# G8CntlA_109_5x19.net
KiCad netlist of a schematic drawn in EAGLE
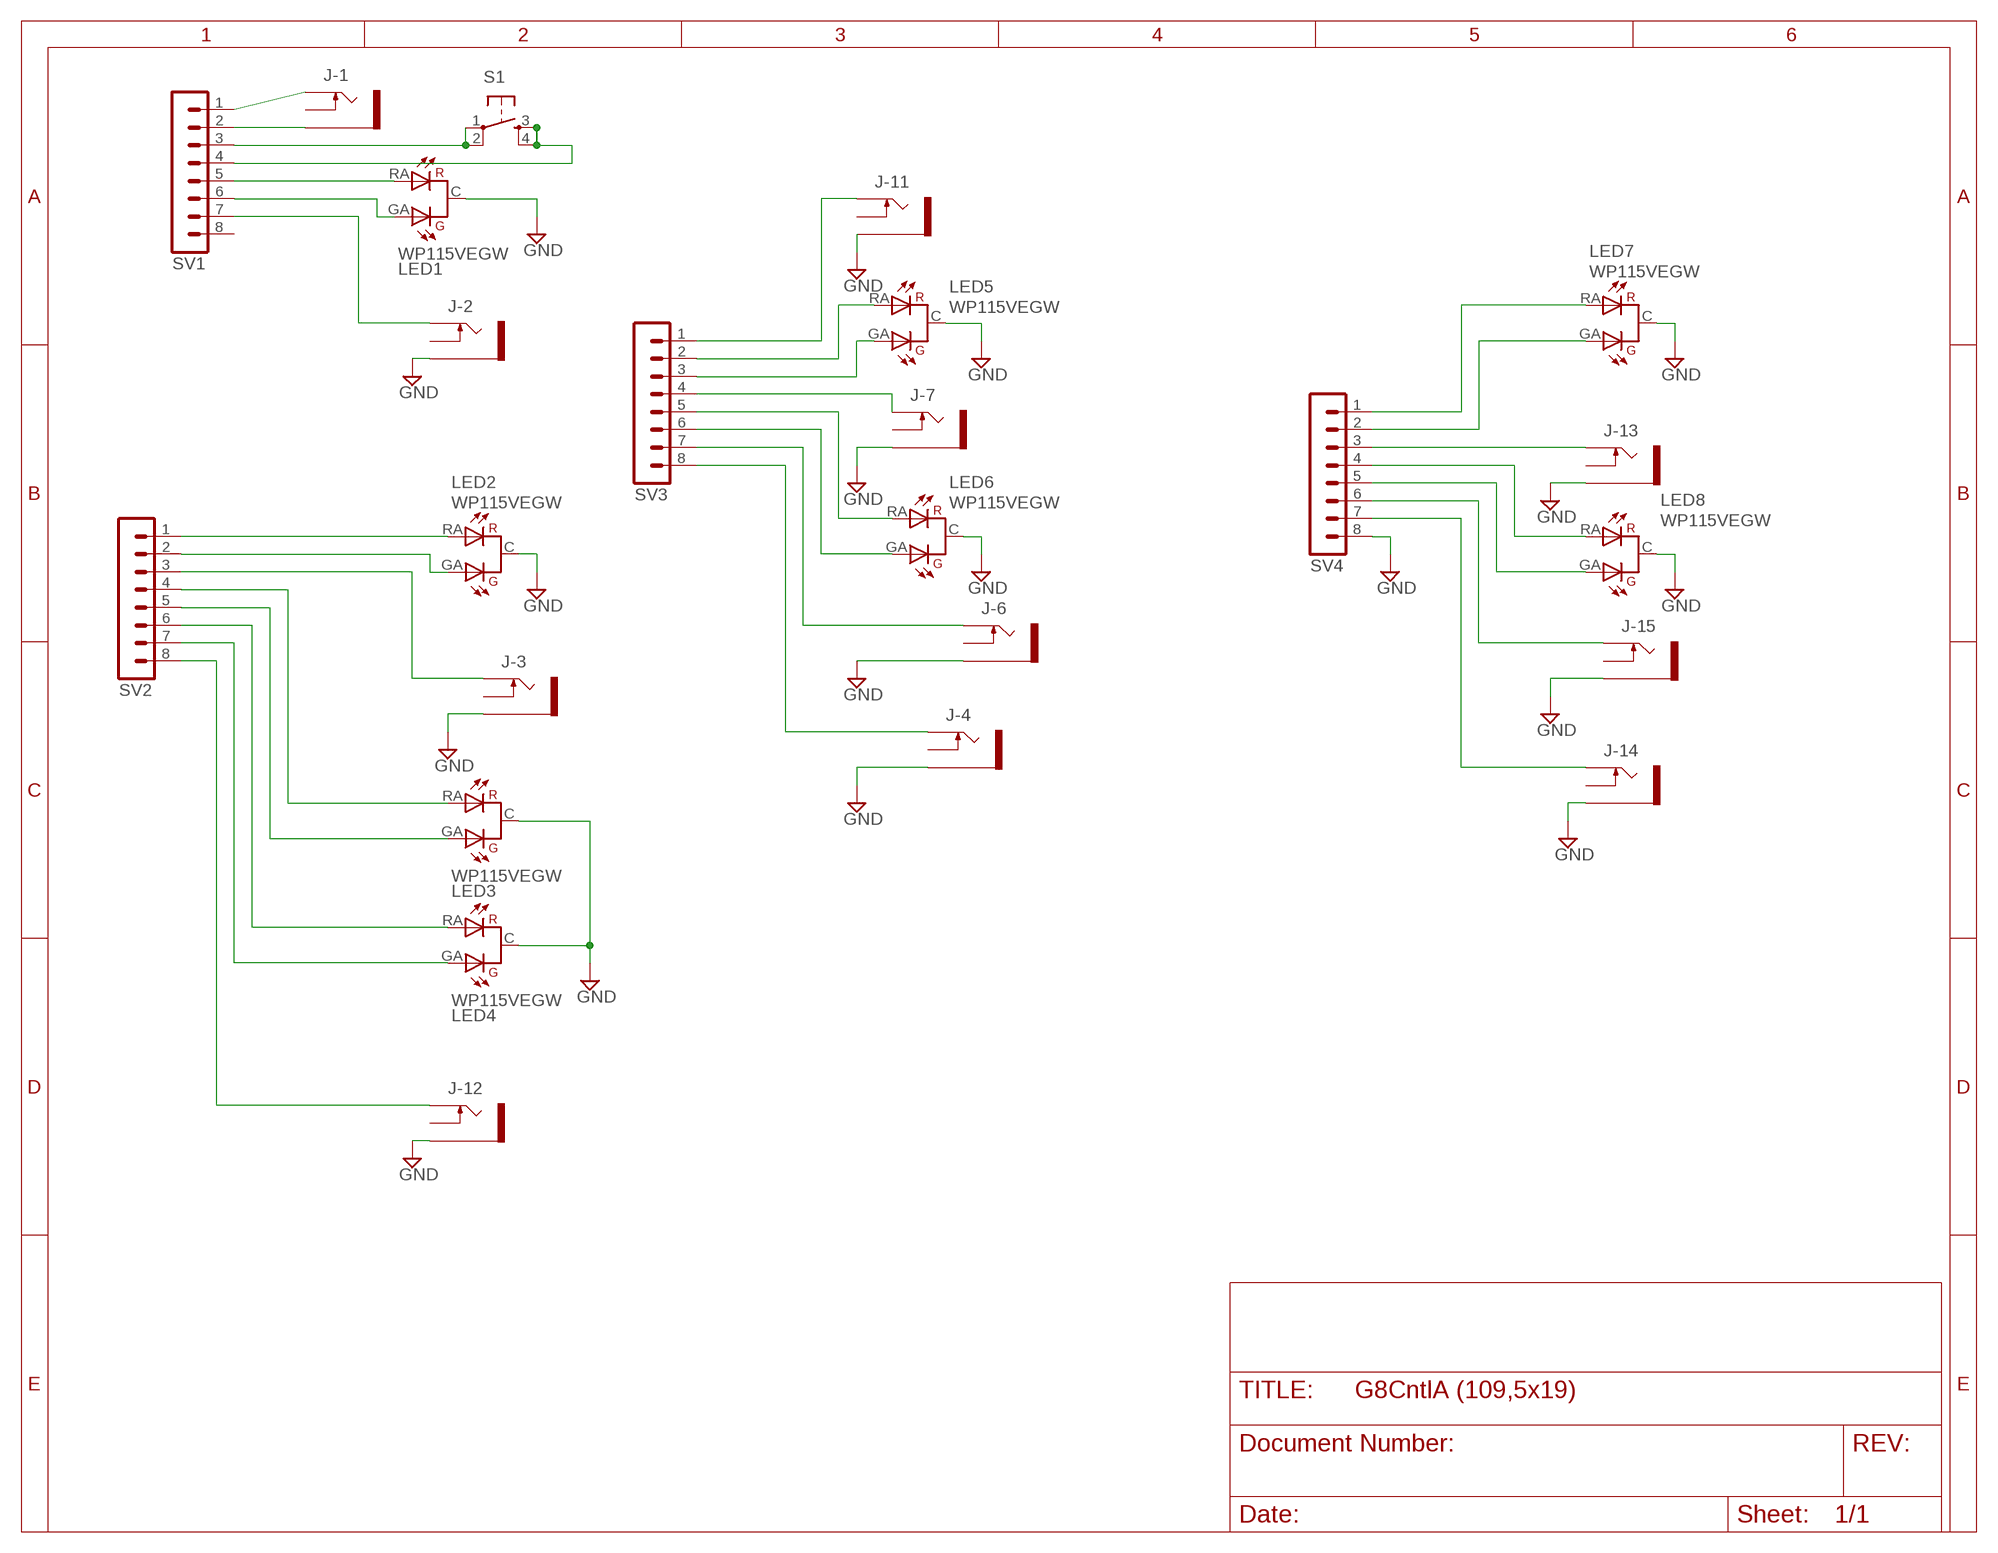
[diagram p0: schematic, sheet 1]

(export (version "E")
  (design (tool "Eeschema 10.0.6"))
  (components
    (comp (ref "J-1")
      (value "THONKICONNNEW")
      (footprint "eagle-import:WQP-PJ301M-12_JACK")
      (libsource (lib "eagle-import") (part "THONKICONNNEW"))
    )
    (comp (ref "J-2")
      (value "THONKICONNNEW")
      (footprint "eagle-import:WQP-PJ301M-12_JACK")
      (libsource (lib "eagle-import") (part "THONKICONNNEW"))
    )
    (comp (ref "J-3")
      (value "THONKICONNNEW")
      (footprint "eagle-import:WQP-PJ301M-12_JACK")
      (libsource (lib "eagle-import") (part "THONKICONNNEW"))
    )
    (comp (ref "J-4")
      (value "THONKICONNNEW")
      (footprint "eagle-import:WQP-PJ301M-12_JACK")
      (libsource (lib "eagle-import") (part "THONKICONNNEW"))
    )
    (comp (ref "J-6")
      (value "THONKICONNNEW")
      (footprint "eagle-import:WQP-PJ301M-12_JACK")
      (libsource (lib "eagle-import") (part "THONKICONNNEW"))
    )
    (comp (ref "J-7")
      (value "THONKICONNNEW")
      (footprint "eagle-import:WQP-PJ301M-12_JACK")
      (libsource (lib "eagle-import") (part "THONKICONNNEW"))
    )
    (comp (ref "J-11")
      (value "THONKICONNNEW")
      (footprint "eagle-import:WQP-PJ301M-12_JACK")
      (libsource (lib "eagle-import") (part "THONKICONNNEW"))
    )
    (comp (ref "J-12")
      (value "THONKICONNNEW")
      (footprint "eagle-import:WQP-PJ301M-12_JACK")
      (libsource (lib "eagle-import") (part "THONKICONNNEW"))
    )
    (comp (ref "J-13")
      (value "THONKICONNNEW")
      (footprint "eagle-import:WQP-PJ301M-12_JACK")
      (libsource (lib "eagle-import") (part "THONKICONNNEW"))
    )
    (comp (ref "J-14")
      (value "THONKICONNNEW")
      (footprint "eagle-import:WQP-PJ301M-12_JACK")
      (libsource (lib "eagle-import") (part "THONKICONNNEW"))
    )
    (comp (ref "J-15")
      (value "THONKICONNNEW")
      (footprint "eagle-import:WQP-PJ301M-12_JACK")
      (libsource (lib "eagle-import") (part "THONKICONNNEW"))
    )
    (comp (ref "LED1")
      (value "WP115VEGW")
      (footprint "eagle-import:WP115VEGW")
      (libsource (lib "eagle-import") (part "WP115VEGW"))
    )
    (comp (ref "LED2")
      (value "WP115VEGW")
      (footprint "eagle-import:WP115VEGW")
      (libsource (lib "eagle-import") (part "WP115VEGW"))
    )
    (comp (ref "LED3")
      (value "WP115VEGW")
      (footprint "eagle-import:WP115VEGW")
      (libsource (lib "eagle-import") (part "WP115VEGW"))
    )
    (comp (ref "LED4")
      (value "WP115VEGW")
      (footprint "eagle-import:WP115VEGW")
      (libsource (lib "eagle-import") (part "WP115VEGW"))
    )
    (comp (ref "LED5")
      (value "WP115VEGW")
      (footprint "eagle-import:WP115VEGW")
      (libsource (lib "eagle-import") (part "WP115VEGW"))
    )
    (comp (ref "LED6")
      (value "WP115VEGW")
      (footprint "eagle-import:WP115VEGW")
      (libsource (lib "eagle-import") (part "WP115VEGW"))
    )
    (comp (ref "LED7")
      (value "WP115VEGW")
      (footprint "eagle-import:WP115VEGW")
      (libsource (lib "eagle-import") (part "WP115VEGW"))
    )
    (comp (ref "LED8")
      (value "WP115VEGW")
      (footprint "eagle-import:WP115VEGW")
      (libsource (lib "eagle-import") (part "WP115VEGW"))
    )
    (comp (ref "S1")
      (value "SPARKFUN_TAC_SWITCHPTH")
      (footprint "eagle-import:SPARKFUN_TACTILE-PTH")
      (libsource (lib "eagle-import") (part "SPARKFUN_TAC_SWITCHPTH"))
    )
    (comp (ref "SV1")
      (value "MA08-1-O")
      (footprint "eagle-import:MA08-OCT")
      (libsource (lib "eagle-import") (part "MA08-1-O"))
    )
    (comp (ref "SV2")
      (value "MA08-1-O")
      (footprint "eagle-import:MA08-OCT")
      (libsource (lib "eagle-import") (part "MA08-1-O"))
    )
    (comp (ref "SV3")
      (value "MA08-1-O")
      (footprint "eagle-import:MA08-OCT")
      (libsource (lib "eagle-import") (part "MA08-1-O"))
    )
    (comp (ref "SV4")
      (value "MA08-1-O")
      (footprint "eagle-import:MA08-OCT")
      (libsource (lib "eagle-import") (part "MA08-1-O"))
    )
  )
  (nets
    (net (code "1") (name "GND") (class "Default")
      (node (ref "J-11") (pin "P$3_SLEEVE") (pinfunction "SLEEVE_P$3_SLEEVE") (pintype "passive"))
      (node (ref "J-12") (pin "P$3_SLEEVE") (pinfunction "SLEEVE_P$3_SLEEVE") (pintype "passive"))
      (node (ref "J-13") (pin "P$3_SLEEVE") (pinfunction "SLEEVE_P$3_SLEEVE") (pintype "passive"))
      (node (ref "J-14") (pin "P$3_SLEEVE") (pinfunction "SLEEVE_P$3_SLEEVE") (pintype "passive"))
      (node (ref "J-15") (pin "P$3_SLEEVE") (pinfunction "SLEEVE_P$3_SLEEVE") (pintype "passive"))
      (node (ref "J-2") (pin "P$3_SLEEVE") (pinfunction "SLEEVE_P$3_SLEEVE") (pintype "passive"))
      (node (ref "J-3") (pin "P$3_SLEEVE") (pinfunction "SLEEVE_P$3_SLEEVE") (pintype "passive"))
      (node (ref "J-4") (pin "P$3_SLEEVE") (pinfunction "SLEEVE_P$3_SLEEVE") (pintype "passive"))
      (node (ref "J-6") (pin "P$3_SLEEVE") (pinfunction "SLEEVE_P$3_SLEEVE") (pintype "passive"))
      (node (ref "J-7") (pin "P$3_SLEEVE") (pinfunction "SLEEVE_P$3_SLEEVE") (pintype "passive"))
      (node (ref "LED1") (pin "C") (pinfunction "C_C") (pintype "bidirectional"))
      (node (ref "LED2") (pin "C") (pinfunction "C_C") (pintype "bidirectional"))
      (node (ref "LED3") (pin "C") (pinfunction "C_C") (pintype "bidirectional"))
      (node (ref "LED4") (pin "C") (pinfunction "C_C") (pintype "bidirectional"))
      (node (ref "LED5") (pin "C") (pinfunction "C_C") (pintype "bidirectional"))
      (node (ref "LED6") (pin "C") (pinfunction "C_C") (pintype "bidirectional"))
      (node (ref "LED7") (pin "C") (pinfunction "C_C") (pintype "bidirectional"))
      (node (ref "LED8") (pin "C") (pinfunction "C_C") (pintype "bidirectional"))
      (node (ref "SV4") (pin "8") (pinfunction "8_8") (pintype "passive"))
    )
    (net (code "2") (name "Net-(J-1-SLEEVE)") (class "Default")
      (node (ref "J-1") (pin "P$3_SLEEVE") (pinfunction "SLEEVE_P$3_SLEEVE") (pintype "passive"))
      (node (ref "SV1") (pin "2") (pinfunction "2_2") (pintype "passive"))
    )
    (net (code "3") (name "Net-(J-1-TIP)") (class "Default")
      (node (ref "J-1") (pin "P$1_TIP") (pinfunction "TIP_P$1_TIP") (pintype "passive"))
      (node (ref "SV1") (pin "1") (pinfunction "1_1") (pintype "passive"))
    )
    (net (code "4") (name "Net-(J-2-TIP)") (class "Default")
      (node (ref "J-2") (pin "P$1_TIP") (pinfunction "TIP_P$1_TIP") (pintype "passive"))
      (node (ref "SV1") (pin "7") (pinfunction "7_7") (pintype "passive"))
    )
    (net (code "5") (name "Net-(J-3-TIP)") (class "Default")
      (node (ref "J-3") (pin "P$1_TIP") (pinfunction "TIP_P$1_TIP") (pintype "passive"))
      (node (ref "SV2") (pin "3") (pinfunction "3_3") (pintype "passive"))
    )
    (net (code "6") (name "Net-(J-4-TIP)") (class "Default")
      (node (ref "J-4") (pin "P$1_TIP") (pinfunction "TIP_P$1_TIP") (pintype "passive"))
      (node (ref "SV3") (pin "8") (pinfunction "8_8") (pintype "passive"))
    )
    (net (code "7") (name "Net-(J-6-TIP)") (class "Default")
      (node (ref "J-6") (pin "P$1_TIP") (pinfunction "TIP_P$1_TIP") (pintype "passive"))
      (node (ref "SV3") (pin "7") (pinfunction "7_7") (pintype "passive"))
    )
    (net (code "8") (name "Net-(J-7-TIP)") (class "Default")
      (node (ref "J-7") (pin "P$1_TIP") (pinfunction "TIP_P$1_TIP") (pintype "passive"))
      (node (ref "SV3") (pin "4") (pinfunction "4_4") (pintype "passive"))
    )
    (net (code "9") (name "Net-(J-11-TIP)") (class "Default")
      (node (ref "J-11") (pin "P$1_TIP") (pinfunction "TIP_P$1_TIP") (pintype "passive"))
      (node (ref "SV3") (pin "1") (pinfunction "1_1") (pintype "passive"))
    )
    (net (code "10") (name "Net-(J-12-TIP)") (class "Default")
      (node (ref "J-12") (pin "P$1_TIP") (pinfunction "TIP_P$1_TIP") (pintype "passive"))
      (node (ref "SV2") (pin "8") (pinfunction "8_8") (pintype "passive"))
    )
    (net (code "11") (name "Net-(J-13-TIP)") (class "Default")
      (node (ref "J-13") (pin "P$1_TIP") (pinfunction "TIP_P$1_TIP") (pintype "passive"))
      (node (ref "SV4") (pin "3") (pinfunction "3_3") (pintype "passive"))
    )
    (net (code "12") (name "Net-(J-14-TIP)") (class "Default")
      (node (ref "J-14") (pin "P$1_TIP") (pinfunction "TIP_P$1_TIP") (pintype "passive"))
      (node (ref "SV4") (pin "7") (pinfunction "7_7") (pintype "passive"))
    )
    (net (code "13") (name "Net-(J-15-TIP)") (class "Default")
      (node (ref "J-15") (pin "P$1_TIP") (pinfunction "TIP_P$1_TIP") (pintype "passive"))
      (node (ref "SV4") (pin "6") (pinfunction "6_6") (pintype "passive"))
    )
    (net (code "14") (name "Net-(LED1-GA)") (class "Default")
      (node (ref "LED1") (pin "RA") (pinfunction "GA_RA") (pintype "bidirectional"))
      (node (ref "SV1") (pin "5") (pinfunction "5_5") (pintype "passive"))
    )
    (net (code "15") (name "Net-(LED1-RA)") (class "Default")
      (node (ref "LED1") (pin "GA") (pinfunction "RA_GA") (pintype "bidirectional"))
      (node (ref "SV1") (pin "6") (pinfunction "6_6") (pintype "passive"))
    )
    (net (code "16") (name "Net-(LED2-GA)") (class "Default")
      (node (ref "LED2") (pin "RA") (pinfunction "GA_RA") (pintype "bidirectional"))
      (node (ref "SV2") (pin "1") (pinfunction "1_1") (pintype "passive"))
    )
    (net (code "17") (name "Net-(LED2-RA)") (class "Default")
      (node (ref "LED2") (pin "GA") (pinfunction "RA_GA") (pintype "bidirectional"))
      (node (ref "SV2") (pin "2") (pinfunction "2_2") (pintype "passive"))
    )
    (net (code "18") (name "Net-(LED3-GA)") (class "Default")
      (node (ref "LED3") (pin "RA") (pinfunction "GA_RA") (pintype "bidirectional"))
      (node (ref "SV2") (pin "4") (pinfunction "4_4") (pintype "passive"))
    )
    (net (code "19") (name "Net-(LED3-RA)") (class "Default")
      (node (ref "LED3") (pin "GA") (pinfunction "RA_GA") (pintype "bidirectional"))
      (node (ref "SV2") (pin "5") (pinfunction "5_5") (pintype "passive"))
    )
    (net (code "20") (name "Net-(LED4-GA)") (class "Default")
      (node (ref "LED4") (pin "RA") (pinfunction "GA_RA") (pintype "bidirectional"))
      (node (ref "SV2") (pin "6") (pinfunction "6_6") (pintype "passive"))
    )
    (net (code "21") (name "Net-(LED4-RA)") (class "Default")
      (node (ref "LED4") (pin "GA") (pinfunction "RA_GA") (pintype "bidirectional"))
      (node (ref "SV2") (pin "7") (pinfunction "7_7") (pintype "passive"))
    )
    (net (code "22") (name "Net-(LED5-GA)") (class "Default")
      (node (ref "LED5") (pin "RA") (pinfunction "GA_RA") (pintype "bidirectional"))
      (node (ref "SV3") (pin "2") (pinfunction "2_2") (pintype "passive"))
    )
    (net (code "23") (name "Net-(LED5-RA)") (class "Default")
      (node (ref "LED5") (pin "GA") (pinfunction "RA_GA") (pintype "bidirectional"))
      (node (ref "SV3") (pin "3") (pinfunction "3_3") (pintype "passive"))
    )
    (net (code "24") (name "Net-(LED6-GA)") (class "Default")
      (node (ref "LED6") (pin "RA") (pinfunction "GA_RA") (pintype "bidirectional"))
      (node (ref "SV3") (pin "5") (pinfunction "5_5") (pintype "passive"))
    )
    (net (code "25") (name "Net-(LED6-RA)") (class "Default")
      (node (ref "LED6") (pin "GA") (pinfunction "RA_GA") (pintype "bidirectional"))
      (node (ref "SV3") (pin "6") (pinfunction "6_6") (pintype "passive"))
    )
    (net (code "26") (name "Net-(LED7-GA)") (class "Default")
      (node (ref "LED7") (pin "RA") (pinfunction "GA_RA") (pintype "bidirectional"))
      (node (ref "SV4") (pin "1") (pinfunction "1_1") (pintype "passive"))
    )
    (net (code "27") (name "Net-(LED7-RA)") (class "Default")
      (node (ref "LED7") (pin "GA") (pinfunction "RA_GA") (pintype "bidirectional"))
      (node (ref "SV4") (pin "2") (pinfunction "2_2") (pintype "passive"))
    )
    (net (code "28") (name "Net-(LED8-GA)") (class "Default")
      (node (ref "LED8") (pin "RA") (pinfunction "GA_RA") (pintype "bidirectional"))
      (node (ref "SV4") (pin "4") (pinfunction "4_4") (pintype "passive"))
    )
    (net (code "29") (name "Net-(LED8-RA)") (class "Default")
      (node (ref "LED8") (pin "GA") (pinfunction "RA_GA") (pintype "bidirectional"))
      (node (ref "SV4") (pin "5") (pinfunction "5_5") (pintype "passive"))
    )
    (net (code "30") (name "Net-(S1-Pad1)") (class "Default")
      (node (ref "S1") (pin "1") (pinfunction "1_1") (pintype "passive"))
      (node (ref "S1") (pin "2") (pinfunction "2_2") (pintype "passive"))
      (node (ref "SV1") (pin "3") (pinfunction "3_3") (pintype "passive"))
    )
    (net (code "31") (name "Net-(S1-Pad3)") (class "Default")
      (node (ref "S1") (pin "3") (pinfunction "3_3") (pintype "passive"))
      (node (ref "S1") (pin "4") (pinfunction "4_4") (pintype "passive"))
      (node (ref "SV1") (pin "4") (pinfunction "4_4") (pintype "passive"))
    )
    (net (code "32") (name "unconnected-(J-1-SWITCH-PadP$2_SWITCH)") (class "Default")
      (node (ref "J-1") (pin "P$2_SWITCH") (pinfunction "SWITCH_P$2_SWITCH") (pintype "passive"))
    )
    (net (code "33") (name "unconnected-(J-2-SWITCH-PadP$2_SWITCH)") (class "Default")
      (node (ref "J-2") (pin "P$2_SWITCH") (pinfunction "SWITCH_P$2_SWITCH") (pintype "passive"))
    )
    (net (code "34") (name "unconnected-(J-3-SWITCH-PadP$2_SWITCH)") (class "Default")
      (node (ref "J-3") (pin "P$2_SWITCH") (pinfunction "SWITCH_P$2_SWITCH") (pintype "passive"))
    )
    (net (code "35") (name "unconnected-(J-4-SWITCH-PadP$2_SWITCH)") (class "Default")
      (node (ref "J-4") (pin "P$2_SWITCH") (pinfunction "SWITCH_P$2_SWITCH") (pintype "passive"))
    )
    (net (code "36") (name "unconnected-(J-6-SWITCH-PadP$2_SWITCH)") (class "Default")
      (node (ref "J-6") (pin "P$2_SWITCH") (pinfunction "SWITCH_P$2_SWITCH") (pintype "passive"))
    )
    (net (code "37") (name "unconnected-(J-7-SWITCH-PadP$2_SWITCH)") (class "Default")
      (node (ref "J-7") (pin "P$2_SWITCH") (pinfunction "SWITCH_P$2_SWITCH") (pintype "passive"))
    )
    (net (code "38") (name "unconnected-(J-11-SWITCH-PadP$2_SWITCH)") (class "Default")
      (node (ref "J-11") (pin "P$2_SWITCH") (pinfunction "SWITCH_P$2_SWITCH") (pintype "passive"))
    )
    (net (code "39") (name "unconnected-(J-12-SWITCH-PadP$2_SWITCH)") (class "Default")
      (node (ref "J-12") (pin "P$2_SWITCH") (pinfunction "SWITCH_P$2_SWITCH") (pintype "passive"))
    )
    (net (code "40") (name "unconnected-(J-13-SWITCH-PadP$2_SWITCH)") (class "Default")
      (node (ref "J-13") (pin "P$2_SWITCH") (pinfunction "SWITCH_P$2_SWITCH") (pintype "passive"))
    )
    (net (code "41") (name "unconnected-(J-14-SWITCH-PadP$2_SWITCH)") (class "Default")
      (node (ref "J-14") (pin "P$2_SWITCH") (pinfunction "SWITCH_P$2_SWITCH") (pintype "passive"))
    )
    (net (code "42") (name "unconnected-(J-15-SWITCH-PadP$2_SWITCH)") (class "Default")
      (node (ref "J-15") (pin "P$2_SWITCH") (pinfunction "SWITCH_P$2_SWITCH") (pintype "passive"))
    )
    (net (code "43") (name "unconnected-(SV1-Pad8)") (class "Default")
      (node (ref "SV1") (pin "8") (pinfunction "8_8") (pintype "passive"))
    )
  )
)
